# clouds_v302_0.net
KiCad netlist of a schematic drawn in Altium Designer
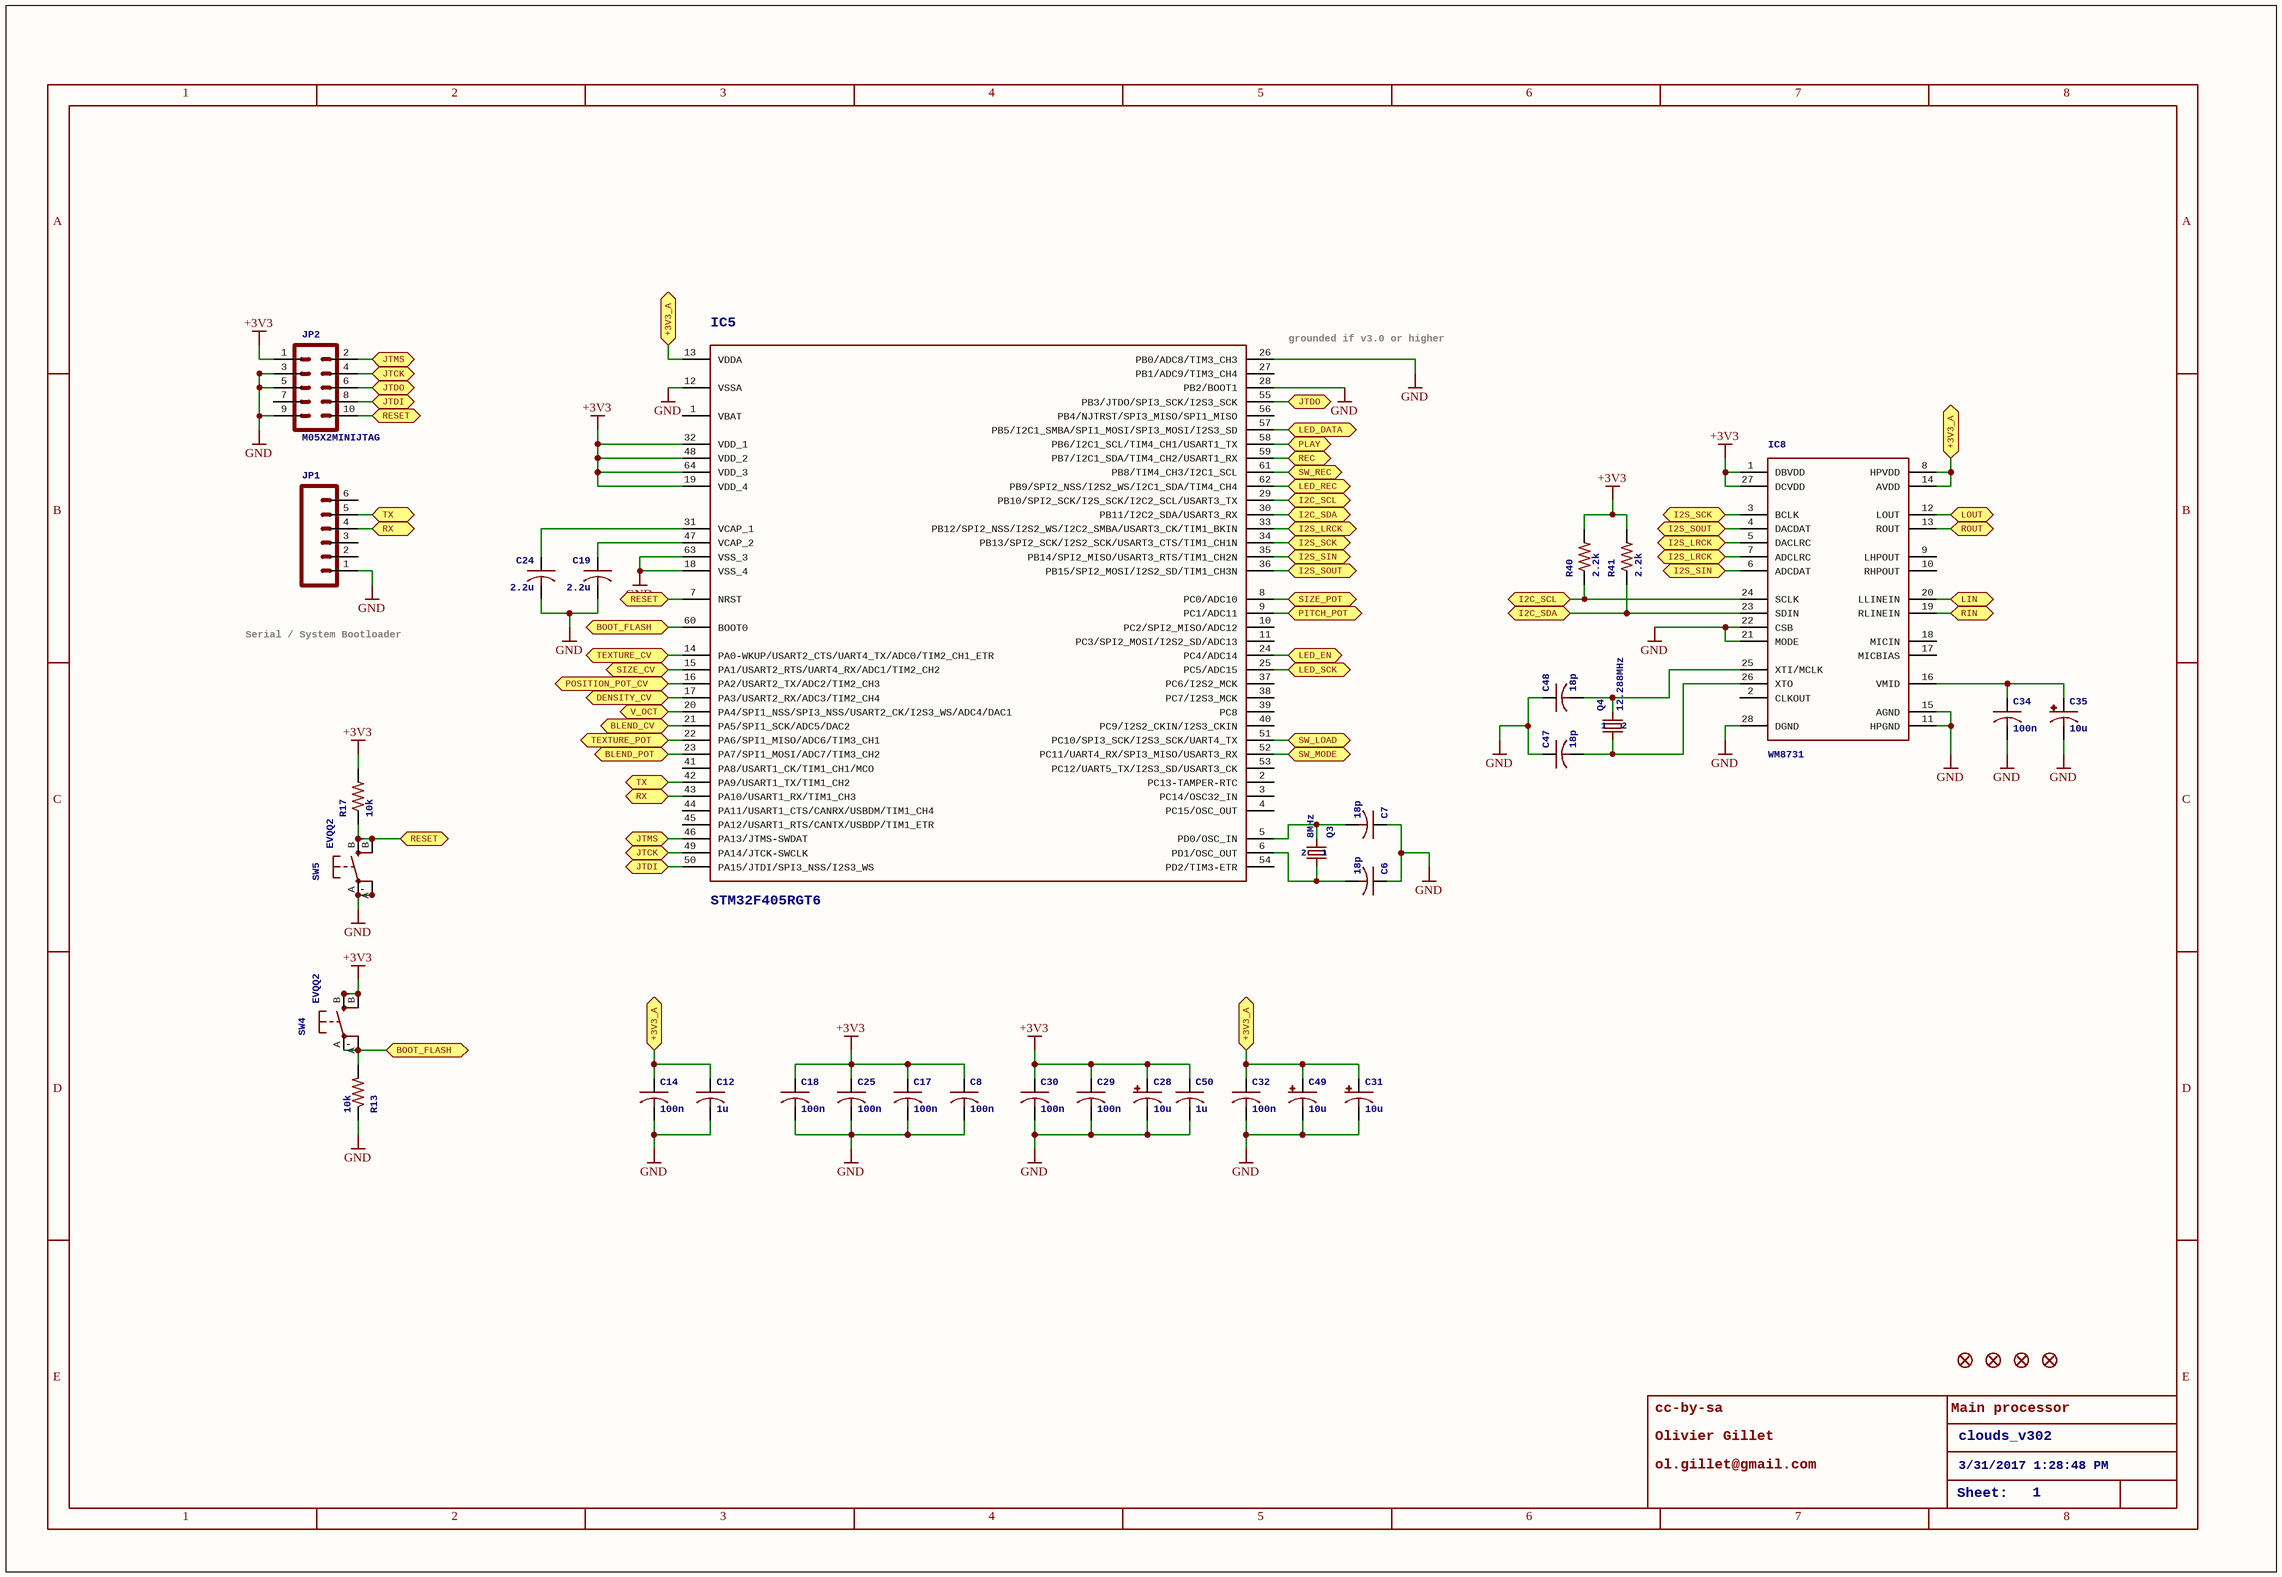
[diagram p0: clouds_v302_0.SchDoc]

(export (version "E")
  (design (tool "Eeschema 10.0.6"))
  (components
    (comp (ref "C6")
      (value "18p")
      (footprint "C0603")
      (description "CAPACITOR, American symbol")
      (libsource (lib "") (part "C-USC0603_1"))
    )
    (comp (ref "C7")
      (value "18p")
      (footprint "C0603")
      (description "CAPACITOR, American symbol")
      (libsource (lib "") (part "C-USC0603_1"))
    )
    (comp (ref "C8")
      (value "100n")
      (footprint "C0603")
      (description "CAPACITOR, American symbol")
      (libsource (lib "rcl") (part "C-USC0603"))
    )
    (comp (ref "C12")
      (value "1u")
      (footprint "C0603")
      (description "CAPACITOR, American symbol")
      (libsource (lib "rcl") (part "C-USC0603"))
    )
    (comp (ref "C14")
      (value "100n")
      (footprint "C0603")
      (description "CAPACITOR, American symbol")
      (libsource (lib "rcl") (part "C-USC0603"))
    )
    (comp (ref "C17")
      (value "100n")
      (footprint "C0603")
      (description "CAPACITOR, American symbol")
      (libsource (lib "rcl") (part "C-USC0603"))
    )
    (comp (ref "C18")
      (value "100n")
      (footprint "C0603")
      (description "CAPACITOR, American symbol")
      (libsource (lib "rcl") (part "C-USC0603"))
    )
    (comp (ref "C19")
      (value "2.2u")
      (footprint "C0805")
      (description "CAPACITOR, American symbol")
      (libsource (lib "rcl") (part "C-USC0805"))
    )
    (comp (ref "C24")
      (value "2.2u")
      (footprint "C0805")
      (description "CAPACITOR, American symbol")
      (libsource (lib "rcl") (part "C-USC0805"))
    )
    (comp (ref "C25")
      (value "100n")
      (footprint "C0603")
      (description "CAPACITOR, American symbol")
      (libsource (lib "rcl") (part "C-USC0603"))
    )
    (comp (ref "C28")
      (value "10u")
      (footprint "PANASONIC_A")
      (description "POLARIZED CAPACITOR, American symbol")
      (libsource (lib "rcl") (part "CPOL-USA"))
    )
    (comp (ref "C29")
      (value "100n")
      (footprint "C0603")
      (description "CAPACITOR, American symbol")
      (libsource (lib "rcl") (part "C-USC0603"))
    )
    (comp (ref "C30")
      (value "100n")
      (footprint "C0603")
      (description "CAPACITOR, American symbol")
      (libsource (lib "rcl") (part "C-USC0603"))
    )
    (comp (ref "C31")
      (value "10u")
      (footprint "PANASONIC_B")
      (description "POLARIZED CAPACITOR, American symbol")
      (libsource (lib "rcl") (part "CPOL-USB"))
    )
    (comp (ref "C32")
      (value "100n")
      (footprint "C0603")
      (description "CAPACITOR, American symbol")
      (libsource (lib "rcl") (part "C-USC0603"))
    )
    (comp (ref "C34")
      (value "100n")
      (footprint "C0603")
      (description "CAPACITOR, American symbol")
      (libsource (lib "rcl") (part "C-USC0603"))
    )
    (comp (ref "C35")
      (value "10u")
      (footprint "PANASONIC_B")
      (description "POLARIZED CAPACITOR, American symbol")
      (libsource (lib "rcl") (part "CPOL-USB"))
    )
    (comp (ref "C47")
      (value "18p")
      (footprint "C0603")
      (description "CAPACITOR, American symbol")
      (libsource (lib "rcl") (part "C-USC0603"))
    )
    (comp (ref "C48")
      (value "18p")
      (footprint "C0603")
      (description "CAPACITOR, American symbol")
      (libsource (lib "rcl") (part "C-USC0603"))
    )
    (comp (ref "C49")
      (value "10u")
      (footprint "PANASONIC_A")
      (description "POLARIZED CAPACITOR, American symbol")
      (libsource (lib "rcl") (part "CPOL-USA"))
    )
    (comp (ref "C50")
      (value "1u")
      (footprint "C0603")
      (description "CAPACITOR, American symbol")
      (libsource (lib "rcl") (part "C-USC0603"))
    )
    (comp (ref "F1")
      (value "FIDUCIAL1X2")
      (footprint "FIDUCIAL-1X2")
      (description "Fiducial Alignment PointsVarious fiducial points for machine vision alignment.")
      (libsource (lib "SparkFun") (part "FIDUCIAL1X2"))
    )
    (comp (ref "F2")
      (value "FIDUCIAL1X2")
      (footprint "FIDUCIAL-1X2")
      (description "Fiducial Alignment PointsVarious fiducial points for machine vision alignment.")
      (libsource (lib "SparkFun") (part "FIDUCIAL1X2"))
    )
    (comp (ref "F3")
      (value "FIDUCIAL1X2")
      (footprint "FIDUCIAL-1X2")
      (description "Fiducial Alignment PointsVarious fiducial points for machine vision alignment.")
      (libsource (lib "SparkFun") (part "FIDUCIAL1X2"))
    )
    (comp (ref "F4")
      (value "FIDUCIAL1X2")
      (footprint "FIDUCIAL-1X2")
      (description "Fiducial Alignment PointsVarious fiducial points for machine vision alignment.")
      (libsource (lib "SparkFun") (part "FIDUCIAL1X2"))
    )
    (comp (ref "IC5")
      (value "STM32F405RGT6")
      (footprint "TQFP-10X10-64")
      (libsource (lib "og-stm32f2") (part "STM32F20X"))
    )
    (comp (ref "IC8")
      (value "WM8731")
      (footprint "SSOP28")
      (fields (field (name "WM8731") "WM8731"))
      (libsource (lib "og-dac") (part "WM8731"))
    )
    (comp (ref "JP1") (value "M06SIP") (footprint "1X06") (libsource (lib "SparkFun") (part "M06SIP")))
    (comp (ref "JP2")
      (value "M05X2MINIJTAG")
      (footprint "2X5-1.27")
      (libsource (lib "og-header") (part "M05X2MINIJTAG"))
    )
    (comp (ref "Q3")
      (value "8MHz")
      (footprint "HC49UP")
      (description "CRYSTAL")
      (fields (field (name "1") "1") (field (name "2") "2"))
      (libsource (lib "crystal") (part "CRYSTALHC49UP"))
    )
    (comp (ref "Q4")
      (value "12.288MHz")
      (footprint "HC49UP")
      (description "CRYSTAL")
      (fields (field (name "1") "1") (field (name "2") "2"))
      (libsource (lib "crystal") (part "CRYSTALHC49UP"))
    )
    (comp (ref "R13")
      (value "10k")
      (footprint "R0603")
      (description "RESISTOR, American symbol")
      (libsource (lib "rcl") (part "R-US_R0603"))
    )
    (comp (ref "R17")
      (value "10k")
      (footprint "R0603")
      (description "RESISTOR, American symbol")
      (libsource (lib "rcl") (part "R-US_R0603"))
    )
    (comp (ref "R40")
      (value "2.2k")
      (footprint "R0603")
      (description "RESISTOR, American symbol")
      (libsource (lib "rcl") (part "R-US_R0603"))
    )
    (comp (ref "R41")
      (value "2.2k")
      (footprint "R0603")
      (description "RESISTOR, American symbol")
      (libsource (lib "rcl") (part "R-US_R0603"))
    )
    (comp (ref "SW4")
      (value "EVQQ2")
      (footprint "EVQ-Q2")
      (description "SMT 6mm switch, EVQQ2 series    http://www.ladyada.net/library/eagle")
      (libsource (lib "adafruit") (part "EVQQ2"))
    )
    (comp (ref "SW5")
      (value "EVQQ2")
      (footprint "EVQ-Q2")
      (description "SMT 6mm switch, EVQQ2 series    http://www.ladyada.net/library/eagle")
      (libsource (lib "adafruit") (part "EVQQ2"))
    )
  )
  (nets
    (net (code "1") (name "+3V3") (class "Default")
      (node (ref "C17") (pin "1") (pinfunction "1_1") (pintype "passive"))
      (node (ref "C18") (pin "1") (pinfunction "1_1") (pintype "passive"))
      (node (ref "C25") (pin "1") (pinfunction "1_1") (pintype "passive"))
      (node (ref "C28") (pin "+") (pinfunction "+_+") (pintype "passive"))
      (node (ref "C29") (pin "1") (pinfunction "1_1") (pintype "passive"))
      (node (ref "C30") (pin "1") (pinfunction "1_1") (pintype "passive"))
      (node (ref "C50") (pin "1") (pinfunction "1_1") (pintype "passive"))
      (node (ref "C8") (pin "1") (pinfunction "1_1") (pintype "passive"))
      (node (ref "IC5") (pin "19") (pinfunction "VDD_4_19") (pintype "power_in"))
      (node (ref "IC5") (pin "32") (pinfunction "VDD_1_32") (pintype "power_in"))
      (node (ref "IC5") (pin "48") (pinfunction "VDD_2_48") (pintype "power_in"))
      (node (ref "IC5") (pin "64") (pinfunction "VDD_3_64") (pintype "power_in"))
      (node (ref "IC8") (pin "1") (pinfunction "DBVDD_1") (pintype "passive"))
      (node (ref "IC8") (pin "27") (pinfunction "DCVDD_27") (pintype "passive"))
      (node (ref "JP2") (pin "1") (pinfunction "1_1") (pintype "passive"))
      (node (ref "R17") (pin "2") (pinfunction "2_2") (pintype "passive"))
      (node (ref "R40") (pin "2") (pinfunction "2_2") (pintype "passive"))
      (node (ref "R41") (pin "2") (pinfunction "2_2") (pintype "passive"))
      (node (ref "SW4") (pin "B") (pinfunction "S_B") (pintype "passive"))
      (node (ref "SW4") (pin "B'") (pinfunction "S1_B'") (pintype "passive"))
    )
    (net (code "2") (name "/+3V3_A") (class "Default")
      (node (ref "C12") (pin "1") (pinfunction "1_1") (pintype "passive"))
      (node (ref "C14") (pin "1") (pinfunction "1_1") (pintype "passive"))
      (node (ref "C31") (pin "+") (pinfunction "+_+") (pintype "passive"))
      (node (ref "C32") (pin "1") (pinfunction "1_1") (pintype "passive"))
      (node (ref "C49") (pin "+") (pinfunction "+_+") (pintype "passive"))
      (node (ref "IC5") (pin "13") (pinfunction "VDDA_13") (pintype "power_in"))
      (node (ref "IC8") (pin "14") (pinfunction "AVDD_14") (pintype "passive"))
      (node (ref "IC8") (pin "8") (pinfunction "HPVDD_8") (pintype "passive"))
    )
    (net (code "3") (name "/BLEND_CV") (class "Default")
      (node (ref "IC5") (pin "21") (pinfunction "PA5/SPI1_SCK/ADC5/DAC2_21") (pintype "passive"))
    )
    (net (code "4") (name "/BLEND_POT") (class "Default")
      (node (ref "IC5") (pin "23") (pinfunction "PA7/SPI1_MOSI/ADC7/TIM3_CH2_23") (pintype "passive"))
    )
    (net (code "5") (name "/BOOT_FLASH") (class "Default")
      (node (ref "IC5") (pin "60") (pinfunction "BOOT0_60") (pintype "passive"))
      (node (ref "R13") (pin "2") (pinfunction "2_2") (pintype "passive"))
      (node (ref "SW4") (pin "A") (pinfunction "P_A") (pintype "passive"))
      (node (ref "SW4") (pin "A'") (pinfunction "P1_A'") (pintype "passive"))
    )
    (net (code "6") (name "/DENSITY_CV") (class "Default")
      (node (ref "IC5") (pin "17") (pinfunction "PA3/USART2_RX/ADC3/TIM2_CH4_17") (pintype "passive"))
    )
    (net (code "7") (name "/I2C_SCL") (class "Default")
      (node (ref "IC5") (pin "29") (pinfunction "PB10/SPI2_SCK/I2S_SCK/I2C2_SCL/USART3_TX_29") (pintype "passive"))
      (node (ref "IC8") (pin "24") (pinfunction "SCLK_24") (pintype "passive"))
      (node (ref "R40") (pin "1") (pinfunction "1_1") (pintype "passive"))
    )
    (net (code "8") (name "/I2C_SDA") (class "Default")
      (node (ref "IC5") (pin "30") (pinfunction "PB11/I2C2_SDA/USART3_RX_30") (pintype "passive"))
      (node (ref "IC8") (pin "23") (pinfunction "SDIN_23") (pintype "passive"))
      (node (ref "R41") (pin "1") (pinfunction "1_1") (pintype "passive"))
    )
    (net (code "9") (name "/I2S_LRCK") (class "Default")
      (node (ref "IC5") (pin "33") (pinfunction "PB12/SPI2_NSS/I2S2_WS/I2C2_SMBA/USART3_CK/TIM1_BKIN_33") (pintype "passive"))
      (node (ref "IC8") (pin "5") (pinfunction "DACLRC_5") (pintype "passive"))
      (node (ref "IC8") (pin "7") (pinfunction "ADCLRC_7") (pintype "passive"))
    )
    (net (code "10") (name "/I2S_SCK") (class "Default")
      (node (ref "IC5") (pin "34") (pinfunction "PB13/SPI2_SCK/I2S2_SCK/USART3_CTS/TIM1_CH1N_34") (pintype "passive"))
      (node (ref "IC8") (pin "3") (pinfunction "BCLK_3") (pintype "passive"))
    )
    (net (code "11") (name "/I2S_SIN") (class "Default")
      (node (ref "IC5") (pin "35") (pinfunction "PB14/SPI2_MISO/USART3_RTS/TIM1_CH2N_35") (pintype "passive"))
      (node (ref "IC8") (pin "6") (pinfunction "ADCDAT_6") (pintype "passive"))
    )
    (net (code "12") (name "/I2S_SOUT") (class "Default")
      (node (ref "IC5") (pin "36") (pinfunction "PB15/SPI2_MOSI/I2S2_SD/TIM1_CH3N_36") (pintype "passive"))
      (node (ref "IC8") (pin "4") (pinfunction "DACDAT_4") (pintype "passive"))
    )
    (net (code "13") (name "/JTCK") (class "Default")
      (node (ref "IC5") (pin "49") (pinfunction "PA14/JTCK-SWCLK_49") (pintype "passive"))
      (node (ref "JP2") (pin "4") (pinfunction "4_4") (pintype "passive"))
    )
    (net (code "14") (name "/JTDI") (class "Default")
      (node (ref "IC5") (pin "50") (pinfunction "PA15/JTDI/SPI3_NSS/I2S3_WS_50") (pintype "passive"))
      (node (ref "JP2") (pin "8") (pinfunction "8_8") (pintype "passive"))
    )
    (net (code "15") (name "/JTDO") (class "Default")
      (node (ref "IC5") (pin "55") (pinfunction "PB3/JTDO/SPI3_SCK/I2S3_SCK_55") (pintype "passive"))
      (node (ref "JP2") (pin "6") (pinfunction "6_6") (pintype "passive"))
    )
    (net (code "16") (name "/JTMS") (class "Default")
      (node (ref "IC5") (pin "46") (pinfunction "PA13/JTMS-SWDAT_46") (pintype "passive"))
      (node (ref "JP2") (pin "2") (pinfunction "2_2") (pintype "passive"))
    )
    (net (code "17") (name "/LED_DATA") (class "Default")
      (node (ref "IC5") (pin "57") (pinfunction "PB5/I2C1_SMBA/SPI1_MOSI/SPI3_MOSI/I2S3_SD_57") (pintype "passive"))
    )
    (net (code "18") (name "/LED_EN") (class "Default")
      (node (ref "IC5") (pin "24") (pinfunction "PC4/ADC14_24") (pintype "passive"))
    )
    (net (code "19") (name "/LED_REC") (class "Default")
      (node (ref "IC5") (pin "62") (pinfunction "PB9/SPI2_NSS/I2S2_WS/I2C1_SDA/TIM4_CH4_62") (pintype "passive"))
    )
    (net (code "20") (name "/LED_SCK") (class "Default")
      (node (ref "IC5") (pin "25") (pinfunction "PC5/ADC15_25") (pintype "passive"))
    )
    (net (code "21") (name "/LIN") (class "Default")
      (node (ref "IC8") (pin "20") (pinfunction "LLINEIN_20") (pintype "passive"))
    )
    (net (code "22") (name "/LOUT") (class "Default")
      (node (ref "IC8") (pin "12") (pinfunction "LOUT_12") (pintype "passive"))
    )
    (net (code "23") (name "/PITCH_POT") (class "Default")
      (node (ref "IC5") (pin "9") (pinfunction "PC1/ADC11_9") (pintype "passive"))
    )
    (net (code "24") (name "/PLAY") (class "Default")
      (node (ref "IC5") (pin "58") (pinfunction "PB6/I2C1_SCL/TIM4_CH1/USART1_TX_58") (pintype "passive"))
    )
    (net (code "25") (name "/POSITION_POT_CV") (class "Default")
      (node (ref "IC5") (pin "16") (pinfunction "PA2/USART2_TX/ADC2/TIM2_CH3_16") (pintype "passive"))
    )
    (net (code "26") (name "/REC") (class "Default")
      (node (ref "IC5") (pin "59") (pinfunction "PB7/I2C1_SDA/TIM4_CH2/USART1_RX_59") (pintype "passive"))
    )
    (net (code "27") (name "/RESET") (class "Default")
      (node (ref "IC5") (pin "7") (pinfunction "NRST_7") (pintype "passive"))
      (node (ref "JP2") (pin "10") (pinfunction "10_10") (pintype "passive"))
      (node (ref "R17") (pin "1") (pinfunction "1_1") (pintype "passive"))
      (node (ref "SW5") (pin "B") (pinfunction "S_B") (pintype "passive"))
      (node (ref "SW5") (pin "B'") (pinfunction "S1_B'") (pintype "passive"))
    )
    (net (code "28") (name "/RIN") (class "Default")
      (node (ref "IC8") (pin "19") (pinfunction "RLINEIN_19") (pintype "passive"))
    )
    (net (code "29") (name "/ROUT") (class "Default")
      (node (ref "IC8") (pin "13") (pinfunction "ROUT_13") (pintype "passive"))
    )
    (net (code "30") (name "/RX") (class "Default")
      (node (ref "IC5") (pin "43") (pinfunction "PA10/USART1_RX/TIM1_CH3_43") (pintype "passive"))
      (node (ref "JP1") (pin "4") (pinfunction "4_4") (pintype "passive"))
    )
    (net (code "31") (name "/SIZE_CV") (class "Default")
      (node (ref "IC5") (pin "15") (pinfunction "PA1/USART2_RTS/UART4_RX/ADC1/TIM2_CH2_15") (pintype "passive"))
    )
    (net (code "32") (name "/SIZE_POT") (class "Default")
      (node (ref "IC5") (pin "8") (pinfunction "PC0/ADC10_8") (pintype "passive"))
    )
    (net (code "33") (name "/SW_LOAD") (class "Default")
      (node (ref "IC5") (pin "51") (pinfunction "PC10/SPI3_SCK/I2S3_SCK/UART4_TX_51") (pintype "passive"))
    )
    (net (code "34") (name "/SW_MODE") (class "Default")
      (node (ref "IC5") (pin "52") (pinfunction "PC11/UART4_RX/SPI3_MISO/USART3_RX_52") (pintype "passive"))
    )
    (net (code "35") (name "/SW_REC") (class "Default")
      (node (ref "IC5") (pin "61") (pinfunction "PB8/TIM4_CH3/I2C1_SCL_61") (pintype "passive"))
    )
    (net (code "36") (name "/TEXTURE_CV") (class "Default")
      (node (ref "IC5") (pin "14") (pinfunction "PA0-WKUP/USART2_CTS/UART4_TX/ADC0/TIM2_CH1_ETR_14") (pintype "passive"))
    )
    (net (code "37") (name "/TEXTURE_POT") (class "Default")
      (node (ref "IC5") (pin "22") (pinfunction "PA6/SPI1_MISO/ADC6/TIM3_CH1_22") (pintype "passive"))
    )
    (net (code "38") (name "/TX") (class "Default")
      (node (ref "IC5") (pin "42") (pinfunction "PA9/USART1_TX/TIM1_CH2_42") (pintype "passive"))
      (node (ref "JP1") (pin "5") (pinfunction "5_5") (pintype "passive"))
    )
    (net (code "39") (name "/V_OCT") (class "Default")
      (node (ref "IC5") (pin "20") (pinfunction "PA4/SPI1_NSS/SPI3_NSS/USART2_CK/I2S3_WS/ADC4/DAC1_20") (pintype "passive"))
    )
    (net (code "40") (name "GND") (class "Default")
      (node (ref "C12") (pin "2") (pinfunction "2_2") (pintype "passive"))
      (node (ref "C14") (pin "2") (pinfunction "2_2") (pintype "passive"))
      (node (ref "C17") (pin "2") (pinfunction "2_2") (pintype "passive"))
      (node (ref "C18") (pin "2") (pinfunction "2_2") (pintype "passive"))
      (node (ref "C19") (pin "2") (pinfunction "2_2") (pintype "passive"))
      (node (ref "C24") (pin "2") (pinfunction "2_2") (pintype "passive"))
      (node (ref "C25") (pin "2") (pinfunction "2_2") (pintype "passive"))
      (node (ref "C28") (pin "-") (pinfunction "-_-") (pintype "passive"))
      (node (ref "C29") (pin "2") (pinfunction "2_2") (pintype "passive"))
      (node (ref "C30") (pin "2") (pinfunction "2_2") (pintype "passive"))
      (node (ref "C31") (pin "-") (pinfunction "-_-") (pintype "passive"))
      (node (ref "C32") (pin "2") (pinfunction "2_2") (pintype "passive"))
      (node (ref "C34") (pin "2") (pinfunction "2_2") (pintype "passive"))
      (node (ref "C35") (pin "-") (pinfunction "-_-") (pintype "passive"))
      (node (ref "C47") (pin "1") (pinfunction "1_1") (pintype "passive"))
      (node (ref "C48") (pin "1") (pinfunction "1_1") (pintype "passive"))
      (node (ref "C49") (pin "-") (pinfunction "-_-") (pintype "passive"))
      (node (ref "C50") (pin "2") (pinfunction "2_2") (pintype "passive"))
      (node (ref "C6") (pin "1") (pinfunction "1_1") (pintype "passive"))
      (node (ref "C7") (pin "1") (pinfunction "1_1") (pintype "passive"))
      (node (ref "C8") (pin "2") (pinfunction "2_2") (pintype "passive"))
      (node (ref "IC5") (pin "12") (pinfunction "VSSA_12") (pintype "power_in"))
      (node (ref "IC5") (pin "18") (pinfunction "VSS_4_18") (pintype "power_in"))
      (node (ref "IC5") (pin "26") (pinfunction "PB0/ADC8/TIM3_CH3_26") (pintype "passive"))
      (node (ref "IC5") (pin "28") (pinfunction "PB2/BOOT1_28") (pintype "passive"))
      (node (ref "IC5") (pin "63") (pinfunction "VSS_3_63") (pintype "power_in"))
      (node (ref "IC8") (pin "11") (pinfunction "HPGND_11") (pintype "passive"))
      (node (ref "IC8") (pin "15") (pinfunction "AGND_15") (pintype "passive"))
      (node (ref "IC8") (pin "21") (pinfunction "MODE_21") (pintype "passive"))
      (node (ref "IC8") (pin "22") (pinfunction "CSB_22") (pintype "passive"))
      (node (ref "IC8") (pin "28") (pinfunction "DGND_28") (pintype "passive"))
      (node (ref "JP1") (pin "1") (pinfunction "1_1") (pintype "passive"))
      (node (ref "JP2") (pin "3") (pinfunction "3_3") (pintype "passive"))
      (node (ref "JP2") (pin "5") (pinfunction "5_5") (pintype "passive"))
      (node (ref "JP2") (pin "9") (pinfunction "9_9") (pintype "passive"))
      (node (ref "R13") (pin "1") (pinfunction "1_1") (pintype "passive"))
      (node (ref "SW5") (pin "A") (pinfunction "P_A") (pintype "passive"))
      (node (ref "SW5") (pin "A'") (pinfunction "P1_A'") (pintype "passive"))
    )
    (net (code "41") (name "Net-(IC5-PD0{slash}OSC_IN)") (class "Default")
      (node (ref "C7") (pin "2") (pinfunction "2_2") (pintype "passive"))
      (node (ref "IC5") (pin "5") (pinfunction "PD0/OSC_IN_5") (pintype "passive"))
      (node (ref "Q3") (pin "2") (pinfunction "2_2") (pintype "passive"))
    )
    (net (code "42") (name "Net-(IC5-PD1{slash}OSC_OUT)") (class "Default")
      (node (ref "C6") (pin "2") (pinfunction "2_2") (pintype "passive"))
      (node (ref "IC5") (pin "6") (pinfunction "PD1/OSC_OUT_6") (pintype "passive"))
      (node (ref "Q3") (pin "1") (pinfunction "1_1") (pintype "passive"))
    )
    (net (code "43") (name "Net-(IC5-VCAP_1)") (class "Default")
      (node (ref "C24") (pin "1") (pinfunction "1_1") (pintype "passive"))
      (node (ref "IC5") (pin "31") (pinfunction "VCAP_1_31") (pintype "power_in"))
    )
    (net (code "44") (name "Net-(IC5-VCAP_2)") (class "Default")
      (node (ref "C19") (pin "1") (pinfunction "1_1") (pintype "passive"))
      (node (ref "IC5") (pin "47") (pinfunction "VCAP_2_47") (pintype "power_in"))
    )
    (net (code "45") (name "Net-(IC8-VMID)") (class "Default")
      (node (ref "C34") (pin "1") (pinfunction "1_1") (pintype "passive"))
      (node (ref "C35") (pin "+") (pinfunction "+_+") (pintype "passive"))
      (node (ref "IC8") (pin "16") (pinfunction "VMID_16") (pintype "passive"))
    )
    (net (code "46") (name "Net-(IC8-XTI{slash}MCLK)") (class "Default")
      (node (ref "C48") (pin "2") (pinfunction "2_2") (pintype "passive"))
      (node (ref "IC8") (pin "25") (pinfunction "XTI/MCLK_25") (pintype "passive"))
      (node (ref "Q4") (pin "2") (pinfunction "2_2") (pintype "passive"))
    )
    (net (code "47") (name "Net-(IC8-XTO)") (class "Default")
      (node (ref "C47") (pin "2") (pinfunction "2_2") (pintype "passive"))
      (node (ref "IC8") (pin "26") (pinfunction "XTO_26") (pintype "passive"))
      (node (ref "Q4") (pin "1") (pinfunction "1_1") (pintype "passive"))
    )
    (net (code "48") (name "unconnected-(IC5-PA8{slash}USART1_CK{slash}TIM1_CH1{slash}MCO-Pad41)") (class "Default")
      (node (ref "IC5") (pin "41") (pinfunction "PA8/USART1_CK/TIM1_CH1/MCO_41") (pintype "passive"))
    )
    (net (code "49") (name "unconnected-(IC5-PA11{slash}USART1_CTS{slash}CANRX{slash}USBDM{slash}TIM1_CH4-Pad44)") (class "Default")
      (node (ref "IC5") (pin "44") (pinfunction "PA11/USART1_CTS/CANRX/USBDM/TIM1_CH4_44") (pintype "passive"))
    )
    (net (code "50") (name "unconnected-(IC5-PA12{slash}USART1_RTS{slash}CANTX{slash}USBDP{slash}TIM1_ETR-Pad45)") (class "Default")
      (node (ref "IC5") (pin "45") (pinfunction "PA12/USART1_RTS/CANTX/USBDP/TIM1_ETR_45") (pintype "passive"))
    )
    (net (code "51") (name "unconnected-(IC5-PB1{slash}ADC9{slash}TIM3_CH4-Pad27)") (class "Default")
      (node (ref "IC5") (pin "27") (pinfunction "PB1/ADC9/TIM3_CH4_27") (pintype "passive"))
    )
    (net (code "52") (name "unconnected-(IC5-PB4{slash}NJTRST{slash}SPI3_MISO{slash}SPI1_MISO-Pad56)") (class "Default")
      (node (ref "IC5") (pin "56") (pinfunction "PB4/NJTRST/SPI3_MISO/SPI1_MISO_56") (pintype "passive"))
    )
    (net (code "53") (name "unconnected-(IC5-PC2{slash}SPI2_MISO{slash}ADC12-Pad10)") (class "Default")
      (node (ref "IC5") (pin "10") (pinfunction "PC2/SPI2_MISO/ADC12_10") (pintype "passive"))
    )
    (net (code "54") (name "unconnected-(IC5-PC3{slash}SPI2_MOSI{slash}I2S2_SD{slash}ADC13-Pad11)") (class "Default")
      (node (ref "IC5") (pin "11") (pinfunction "PC3/SPI2_MOSI/I2S2_SD/ADC13_11") (pintype "passive"))
    )
    (net (code "55") (name "unconnected-(IC5-PC6{slash}I2S2_MCK-Pad37)") (class "Default")
      (node (ref "IC5") (pin "37") (pinfunction "PC6/I2S2_MCK_37") (pintype "passive"))
    )
    (net (code "56") (name "unconnected-(IC5-PC7{slash}I2S3_MCK-Pad38)") (class "Default")
      (node (ref "IC5") (pin "38") (pinfunction "PC7/I2S3_MCK_38") (pintype "passive"))
    )
    (net (code "57") (name "unconnected-(IC5-PC8-Pad39)") (class "Default")
      (node (ref "IC5") (pin "39") (pinfunction "PC8_39") (pintype "passive"))
    )
    (net (code "58") (name "unconnected-(IC5-PC9{slash}I2S2_CKIN{slash}I2S3_CKIN-Pad40)") (class "Default")
      (node (ref "IC5") (pin "40") (pinfunction "PC9/I2S2_CKIN/I2S3_CKIN_40") (pintype "passive"))
    )
    (net (code "59") (name "unconnected-(IC5-PC12{slash}UART5_TX{slash}I2S3_SD{slash}USART3_CK-Pad53)") (class "Default")
      (node (ref "IC5") (pin "53") (pinfunction "PC12/UART5_TX/I2S3_SD/USART3_CK_53") (pintype "passive"))
    )
    (net (code "60") (name "unconnected-(IC5-PC13-TAMPER-RTC-Pad2)") (class "Default")
      (node (ref "IC5") (pin "2") (pinfunction "PC13-TAMPER-RTC_2") (pintype "passive"))
    )
    (net (code "61") (name "unconnected-(IC5-PC14{slash}OSC32_IN-Pad3)") (class "Default")
      (node (ref "IC5") (pin "3") (pinfunction "PC14/OSC32_IN_3") (pintype "passive"))
    )
    (net (code "62") (name "unconnected-(IC5-PC15{slash}OSC_OUT-Pad4)") (class "Default")
      (node (ref "IC5") (pin "4") (pinfunction "PC15/OSC_OUT_4") (pintype "passive"))
    )
    (net (code "63") (name "unconnected-(IC5-PD2{slash}TIM3-ETR-Pad54)") (class "Default")
      (node (ref "IC5") (pin "54") (pinfunction "PD2/TIM3-ETR_54") (pintype "passive"))
    )
    (net (code "64") (name "unconnected-(IC5-VBAT-Pad1)") (class "Default")
      (node (ref "IC5") (pin "1") (pinfunction "VBAT_1") (pintype "power_in"))
    )
    (net (code "65") (name "unconnected-(IC8-CLKOUT-Pad2)") (class "Default")
      (node (ref "IC8") (pin "2") (pinfunction "CLKOUT_2") (pintype "passive"))
    )
    (net (code "66") (name "unconnected-(IC8-LHPOUT-Pad9)") (class "Default")
      (node (ref "IC8") (pin "9") (pinfunction "LHPOUT_9") (pintype "passive"))
    )
    (net (code "67") (name "unconnected-(IC8-MICBIAS-Pad17)") (class "Default")
      (node (ref "IC8") (pin "17") (pinfunction "MICBIAS_17") (pintype "passive"))
    )
    (net (code "68") (name "unconnected-(IC8-MICIN-Pad18)") (class "Default")
      (node (ref "IC8") (pin "18") (pinfunction "MICIN_18") (pintype "passive"))
    )
    (net (code "69") (name "unconnected-(IC8-RHPOUT-Pad10)") (class "Default")
      (node (ref "IC8") (pin "10") (pinfunction "RHPOUT_10") (pintype "passive"))
    )
    (net (code "70") (name "unconnected-(JP1-Pad2)") (class "Default")
      (node (ref "JP1") (pin "2") (pinfunction "2_2") (pintype "passive"))
    )
    (net (code "71") (name "unconnected-(JP1-Pad3)") (class "Default")
      (node (ref "JP1") (pin "3") (pinfunction "3_3") (pintype "passive"))
    )
    (net (code "72") (name "unconnected-(JP1-Pad6)") (class "Default")
      (node (ref "JP1") (pin "6") (pinfunction "6_6") (pintype "passive"))
    )
    (net (code "73") (name "unconnected-(JP2-Pad7)") (class "Default")
      (node (ref "JP2") (pin "7") (pinfunction "7_7") (pintype "passive"))
    )
  )
)
